# CW308T_STM32F415_Micro.net
KiCad netlist of a schematic drawn in Altium Designer
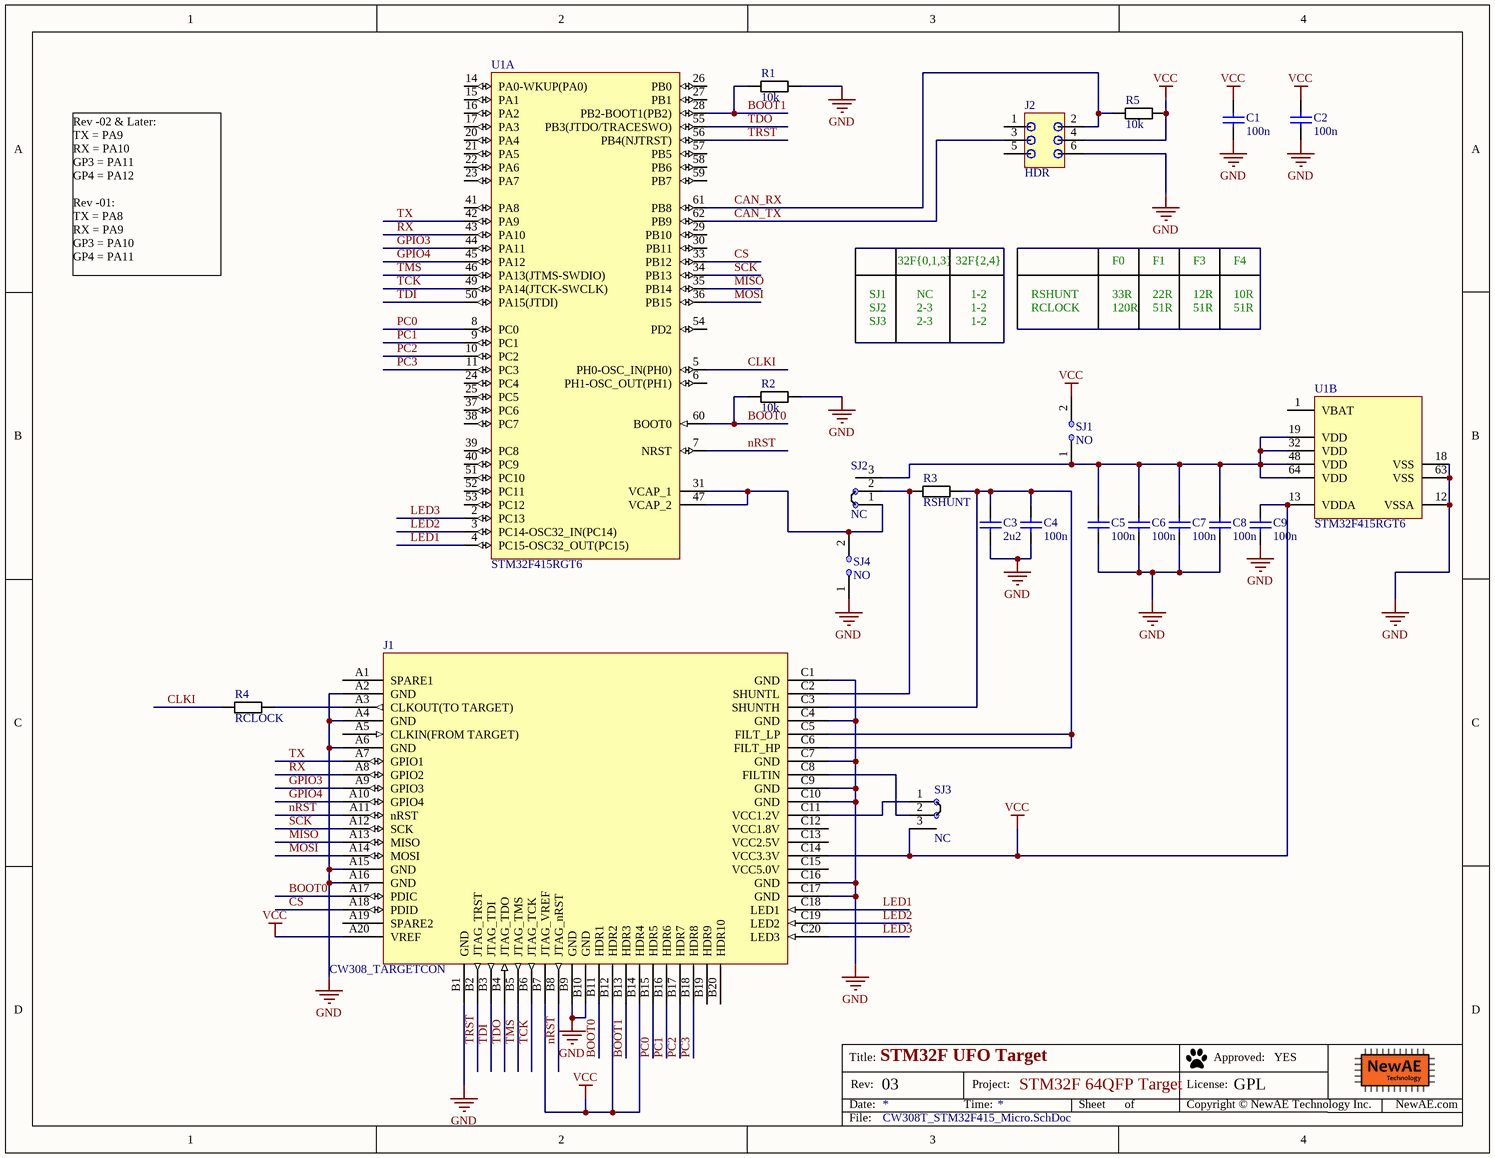
[diagram p0: CW308T_STM32F415_Micro.SchDoc]

(export (version "E")
  (design (tool "Eeschema 10.0.6"))
  (components
    (comp (ref "C1")
      (value "100n")
      (footprint "CAPC0603_M")
      (description "100n, 0603")
      (fields (field (name "PART NUMBER") "CCHIP-100n-0603"))
      (libsource (lib "NewAE_AltiumLib") (part "CAP"))
    )
    (comp (ref "C2")
      (value "100n")
      (footprint "CAPC0603_M")
      (description "100n, 0603")
      (fields (field (name "PART NUMBER") "CCHIP-100n-0603"))
      (libsource (lib "NewAE_AltiumLib") (part "CAP"))
    )
    (comp (ref "C3")
      (value "2u2")
      (footprint "CAPC0603_M")
      (description "2u2, 0603")
      (fields (field (name "PART NUMBER") "CCHIP-2u2-0603"))
      (libsource (lib "NewAE_AltiumLib") (part "CAP"))
    )
    (comp (ref "C4")
      (value "100n")
      (footprint "CAPC0603_M")
      (description "100n, 0603")
      (fields (field (name "PART NUMBER") "CCHIP-100n-0603"))
      (libsource (lib "NewAE_AltiumLib") (part "CAP"))
    )
    (comp (ref "C5")
      (value "100n")
      (footprint "CAPC0603_M")
      (description "100n, 0603")
      (fields (field (name "PART NUMBER") "CCHIP-100n-0603"))
      (libsource (lib "NewAE_AltiumLib") (part "CAP"))
    )
    (comp (ref "C6")
      (value "100n")
      (footprint "CAPC0603_M")
      (description "100n, 0603")
      (fields (field (name "PART NUMBER") "CCHIP-100n-0603"))
      (libsource (lib "NewAE_AltiumLib") (part "CAP"))
    )
    (comp (ref "C7")
      (value "100n")
      (footprint "CAPC0603_M")
      (description "100n, 0603")
      (fields (field (name "PART NUMBER") "CCHIP-100n-0603"))
      (libsource (lib "NewAE_AltiumLib") (part "CAP"))
    )
    (comp (ref "C8")
      (value "100n")
      (footprint "CAPC0603_M")
      (description "100n, 0603")
      (fields (field (name "PART NUMBER") "CCHIP-100n-0603"))
      (libsource (lib "NewAE_AltiumLib") (part "CAP"))
    )
    (comp (ref "C9")
      (value "100n")
      (footprint "CAPC0603_M")
      (description "100n, 0603")
      (fields (field (name "PART NUMBER") "CCHIP-100n-0603"))
      (libsource (lib "NewAE_AltiumLib") (part "CAP"))
    )
    (comp (ref "J1")
      (value "CW308_TARGETCON")
      (footprint "CW308_TBOARD_CONN")
      (description "CW308 \"Standard\" Target Board Connector")
      (fields (field (name "PART NUMBER") "CW308_TBOARD"))
      (libsource (lib "NewAE_AltiumLib") (part "CW308_TBOARD"))
    )
    (comp (ref "J2")
      (value "HDR")
      (footprint "HDR_6PIN_2ROW_SHROUD")
      (description "HDR, Male, 6-Pin, 2 Row, Shrouded")
      (fields (field (name "PART NUMBER") "HDR_6PIN_2ROW_SHROUD"))
      (libsource (lib "NewAE_AltiumLib") (part "CON6_2ROW"))
    )
    (comp (ref "R1")
      (value "10k")
      (footprint "RESC1608X55N")
      (description "10k res, 0603, 1%, 1/10W")
      (fields (field (name "PART NUMBER") "RCHIP-10K-0603") (field (name "TOLERANCE") "1%"))
      (libsource (lib "NewAE_AltiumLib") (part "RES-EU"))
    )
    (comp (ref "R2")
      (value "10k")
      (footprint "RESC1608X55N")
      (description "10k res, 0603, 1%, 1/10W")
      (fields (field (name "PART NUMBER") "RCHIP-10K-0603") (field (name "TOLERANCE") "1%"))
      (libsource (lib "NewAE_AltiumLib") (part "RES-EU"))
    )
    (comp (ref "R3")
      (value "RSHUNT")
      (footprint "RESC1608X55N")
      (description "10R res, 0603, 1%, 1/10W")
      (fields (field (name "PART NUMBER") "RCHIP-10R-0603") (field (name "TOLERANCE") "1%"))
      (libsource (lib "NewAE_AltiumLib") (part "RES-EU"))
    )
    (comp (ref "R4")
      (value "RCLOCK")
      (footprint "RESC1608X55N")
      (description "100R res, 0603, 1%, 1/10W")
      (fields (field (name "PART NUMBER") "RCHIP-100R-0603") (field (name "TOLERANCE") "1%"))
      (libsource (lib "NewAE_AltiumLib") (part "RES-EU"))
    )
    (comp (ref "R5")
      (value "10k")
      (footprint "RESC1608X55N")
      (description "10k res, 0603, 1%, 1/10W")
      (fields (field (name "PART NUMBER") "RCHIP-10K-0603") (field (name "TOLERANCE") "1%"))
      (libsource (lib "NewAE_AltiumLib") (part "RES-EU"))
    )
    (comp (ref "SJ1")
      (value "NO")
      (footprint "SJ_2S_NO")
      (description "Solder Jumper, NO")
      (fields (field (name "PART NUMBER") "SJ_2S_NO"))
      (libsource (lib "NewAE_AltiumLib") (part "SJ_2S_NO"))
    )
    (comp (ref "SJ2")
      (value "NC")
      (footprint "SJ_3S_NC12")
      (description "Solder Jumper, NC")
      (fields (field (name "PART NUMBER") "SJ_3S_12JMP"))
      (libsource (lib "NewAE_AltiumLib") (part "SJ_3S_12JMP"))
    )
    (comp (ref "SJ3")
      (value "NC")
      (footprint "SJ_3S_NC12")
      (description "Solder Jumper, NC")
      (fields (field (name "PART NUMBER") "SJ_3S_12JMP"))
      (libsource (lib "NewAE_AltiumLib") (part "SJ_3S_12JMP"))
    )
    (comp (ref "SJ4")
      (value "NO")
      (footprint "SJ_2S_NO")
      (description "Solder Jumper, NO")
      (fields (field (name "PART NUMBER") "SJ_2S_NO"))
      (libsource (lib "NewAE_AltiumLib") (part "SJ_2S_NO"))
    )
    (comp (ref "U1")
      (value "STM32F415RGT6")
      (footprint "STM-LQFP64_V")
      (fields (field (name "MANUFACTURER") "STMicroelectronics"))
      (libsource (lib "Altium Content Vault") (part "MC-ARM-STM32F4X5-SQ64"))
    )
  )
  (nets
    (net (code "1") (name "/BOOT0") (class "Default")
      (node (ref "J1") (pin "A17") (pinfunction "PDIC_A17") (pintype "bidirectional"))
      (node (ref "J1") (pin "B11") (pinfunction "HDR1_B11") (pintype "passive"))
      (node (ref "R2") (pin "1") (pinfunction "1_1") (pintype "passive"))
      (node (ref "U1") (pin "60") (pinfunction "BOOT0_60") (pintype "input"))
    )
    (net (code "2") (name "/BOOT1") (class "Default")
      (node (ref "J1") (pin "B13") (pinfunction "HDR3_B13") (pintype "passive"))
      (node (ref "R1") (pin "1") (pinfunction "1_1") (pintype "passive"))
      (node (ref "U1") (pin "28") (pinfunction "PB2-BOOT1(PB2)_28") (pintype "bidirectional"))
    )
    (net (code "3") (name "/CAN_RX") (class "Default")
      (node (ref "J2") (pin "2") (pinfunction "2_2") (pintype "passive"))
      (node (ref "R5") (pin "1") (pinfunction "1_1") (pintype "passive"))
      (node (ref "U1") (pin "61") (pinfunction "PB8_61") (pintype "bidirectional"))
    )
    (net (code "4") (name "/CAN_TX") (class "Default")
      (node (ref "J2") (pin "3") (pinfunction "3_3") (pintype "passive"))
      (node (ref "U1") (pin "62") (pinfunction "PB9_62") (pintype "bidirectional"))
    )
    (net (code "5") (name "/CLKI") (class "Default")
      (node (ref "R4") (pin "1") (pinfunction "1_1") (pintype "passive"))
      (node (ref "U1") (pin "5") (pinfunction "PH0-OSC_IN(PH0)_5") (pintype "bidirectional"))
    )
    (net (code "6") (name "/CS") (class "Default")
      (node (ref "J1") (pin "A18") (pinfunction "PDID_A18") (pintype "bidirectional"))
      (node (ref "U1") (pin "33") (pinfunction "PB12_33") (pintype "bidirectional"))
    )
    (net (code "7") (name "/GPIO3") (class "Default")
      (node (ref "J1") (pin "A9") (pinfunction "GPIO3_A9") (pintype "bidirectional"))
      (node (ref "U1") (pin "44") (pinfunction "PA11_44") (pintype "bidirectional"))
    )
    (net (code "8") (name "/GPIO4") (class "Default")
      (node (ref "J1") (pin "A10") (pinfunction "GPIO4_A10") (pintype "bidirectional"))
      (node (ref "U1") (pin "45") (pinfunction "PA12_45") (pintype "bidirectional"))
    )
    (net (code "9") (name "/LED1") (class "Default")
      (node (ref "J1") (pin "C18") (pinfunction "LED1_C18") (pintype "input"))
      (node (ref "U1") (pin "4") (pinfunction "PC15-OSC32_OUT(PC15)_4") (pintype "bidirectional"))
    )
    (net (code "10") (name "/LED2") (class "Default")
      (node (ref "J1") (pin "C19") (pinfunction "LED2_C19") (pintype "input"))
      (node (ref "U1") (pin "3") (pinfunction "PC14-OSC32_IN(PC14)_3") (pintype "bidirectional"))
    )
    (net (code "11") (name "/LED3") (class "Default")
      (node (ref "J1") (pin "C20") (pinfunction "LED3_C20") (pintype "input"))
      (node (ref "U1") (pin "2") (pinfunction "PC13_2") (pintype "bidirectional"))
    )
    (net (code "12") (name "/MISO") (class "Default")
      (node (ref "J1") (pin "A13") (pinfunction "MISO_A13") (pintype "bidirectional"))
      (node (ref "U1") (pin "35") (pinfunction "PB14_35") (pintype "bidirectional"))
    )
    (net (code "13") (name "/MOSI") (class "Default")
      (node (ref "J1") (pin "A14") (pinfunction "MOSI_A14") (pintype "bidirectional"))
      (node (ref "U1") (pin "36") (pinfunction "PB15_36") (pintype "bidirectional"))
    )
    (net (code "14") (name "/PC0") (class "Default")
      (node (ref "J1") (pin "B15") (pinfunction "HDR5_B15") (pintype "passive"))
      (node (ref "U1") (pin "8") (pinfunction "PC0_8") (pintype "bidirectional"))
    )
    (net (code "15") (name "/PC1") (class "Default")
      (node (ref "J1") (pin "B16") (pinfunction "HDR6_B16") (pintype "passive"))
      (node (ref "U1") (pin "9") (pinfunction "PC1_9") (pintype "bidirectional"))
    )
    (net (code "16") (name "/PC2") (class "Default")
      (node (ref "J1") (pin "B17") (pinfunction "HDR7_B17") (pintype "passive"))
      (node (ref "U1") (pin "10") (pinfunction "PC2_10") (pintype "bidirectional"))
    )
    (net (code "17") (name "/PC3") (class "Default")
      (node (ref "J1") (pin "B18") (pinfunction "HDR8_B18") (pintype "passive"))
      (node (ref "U1") (pin "11") (pinfunction "PC3_11") (pintype "bidirectional"))
    )
    (net (code "18") (name "/RX") (class "Default")
      (node (ref "J1") (pin "A8") (pinfunction "GPIO2_A8") (pintype "bidirectional"))
      (node (ref "U1") (pin "43") (pinfunction "PA10_43") (pintype "bidirectional"))
    )
    (net (code "19") (name "/SCK") (class "Default")
      (node (ref "J1") (pin "A12") (pinfunction "SCK_A12") (pintype "bidirectional"))
      (node (ref "U1") (pin "34") (pinfunction "PB13_34") (pintype "bidirectional"))
    )
    (net (code "20") (name "/TCK") (class "Default")
      (node (ref "J1") (pin "B6") (pinfunction "JTAG_TCK_B6") (pintype "output"))
      (node (ref "U1") (pin "49") (pinfunction "PA14(JTCK-SWCLK)_49") (pintype "bidirectional"))
    )
    (net (code "21") (name "/TDI") (class "Default")
      (node (ref "J1") (pin "B3") (pinfunction "JTAG_TDI_B3") (pintype "output"))
      (node (ref "U1") (pin "50") (pinfunction "PA15(JTDI)_50") (pintype "bidirectional"))
    )
    (net (code "22") (name "/TDO") (class "Default")
      (node (ref "J1") (pin "B4") (pinfunction "JTAG_TDO_B4") (pintype "input"))
      (node (ref "U1") (pin "55") (pinfunction "PB3(JTDO/TRACESWO)_55") (pintype "bidirectional"))
    )
    (net (code "23") (name "/TMS") (class "Default")
      (node (ref "J1") (pin "B5") (pinfunction "JTAG_TMS_B5") (pintype "output"))
      (node (ref "U1") (pin "46") (pinfunction "PA13(JTMS-SWDIO)_46") (pintype "bidirectional"))
    )
    (net (code "24") (name "/TRST") (class "Default")
      (node (ref "J1") (pin "B2") (pinfunction "JTAG_TRST_B2") (pintype "output"))
      (node (ref "U1") (pin "56") (pinfunction "PB4(NJTRST)_56") (pintype "bidirectional"))
    )
    (net (code "25") (name "/TX") (class "Default")
      (node (ref "J1") (pin "A7") (pinfunction "GPIO1_A7") (pintype "bidirectional"))
      (node (ref "U1") (pin "42") (pinfunction "PA9_42") (pintype "bidirectional"))
    )
    (net (code "26") (name "/nRST") (class "Default")
      (node (ref "J1") (pin "A11") (pinfunction "nRST_A11") (pintype "bidirectional"))
      (node (ref "J1") (pin "B8") (pinfunction "JTAG_nRST_B8") (pintype "output"))
      (node (ref "U1") (pin "7") (pinfunction "NRST_7") (pintype "bidirectional"))
    )
    (net (code "27") (name "GND") (class "Default")
      (node (ref "C1") (pin "2") (pinfunction "2_2") (pintype "passive"))
      (node (ref "C2") (pin "2") (pinfunction "2_2") (pintype "passive"))
      (node (ref "C3") (pin "2") (pinfunction "2_2") (pintype "passive"))
      (node (ref "C4") (pin "2") (pinfunction "2_2") (pintype "passive"))
      (node (ref "C5") (pin "2") (pinfunction "2_2") (pintype "passive"))
      (node (ref "C6") (pin "2") (pinfunction "2_2") (pintype "passive"))
      (node (ref "C7") (pin "2") (pinfunction "2_2") (pintype "passive"))
      (node (ref "C8") (pin "2") (pinfunction "2_2") (pintype "passive"))
      (node (ref "C9") (pin "2") (pinfunction "2_2") (pintype "passive"))
      (node (ref "J1") (pin "A15") (pinfunction "GND_A15") (pintype "passive"))
      (node (ref "J1") (pin "A16") (pinfunction "GND_A16") (pintype "passive"))
      (node (ref "J1") (pin "A2") (pinfunction "GND_A2") (pintype "passive"))
      (node (ref "J1") (pin "A4") (pinfunction "GND_A4") (pintype "passive"))
      (node (ref "J1") (pin "A6") (pinfunction "GND_A6") (pintype "power_in"))
      (node (ref "J1") (pin "B1") (pinfunction "GND_B1") (pintype "passive"))
      (node (ref "J1") (pin "B10") (pinfunction "GND_B10") (pintype "passive"))
      (node (ref "J1") (pin "B9") (pinfunction "GND_B9") (pintype "passive"))
      (node (ref "J1") (pin "C1") (pinfunction "GND_C1") (pintype "power_in"))
      (node (ref "J1") (pin "C10") (pinfunction "GND_C10") (pintype "power_in"))
      (node (ref "J1") (pin "C16") (pinfunction "GND_C16") (pintype "power_in"))
      (node (ref "J1") (pin "C17") (pinfunction "GND_C17") (pintype "power_in"))
      (node (ref "J1") (pin "C4") (pinfunction "GND_C4") (pintype "power_in"))
      (node (ref "J1") (pin "C7") (pinfunction "GND_C7") (pintype "power_in"))
      (node (ref "J1") (pin "C9") (pinfunction "GND_C9") (pintype "power_in"))
      (node (ref "J2") (pin "6") (pinfunction "6_6") (pintype "passive"))
      (node (ref "R1") (pin "2") (pinfunction "2_2") (pintype "passive"))
      (node (ref "R2") (pin "2") (pinfunction "2_2") (pintype "passive"))
      (node (ref "SJ4") (pin "1") (pinfunction "1_1") (pintype "passive"))
      (node (ref "U1") (pin "12") (pinfunction "VSSA_12") (pintype "power_in"))
      (node (ref "U1") (pin "18") (pinfunction "VSS_18") (pintype "power_in"))
      (node (ref "U1") (pin "63") (pinfunction "VSS_63") (pintype "power_in"))
    )
    (net (code "28") (name "Net-(C5-Pad1)") (class "Default")
      (node (ref "C5") (pin "1") (pinfunction "1_1") (pintype "passive"))
      (node (ref "C6") (pin "1") (pinfunction "1_1") (pintype "passive"))
      (node (ref "C7") (pin "1") (pinfunction "1_1") (pintype "passive"))
      (node (ref "C8") (pin "1") (pinfunction "1_1") (pintype "passive"))
      (node (ref "SJ1") (pin "1") (pinfunction "1_1") (pintype "passive"))
      (node (ref "SJ2") (pin "3") (pinfunction "3_3") (pintype "passive"))
      (node (ref "U1") (pin "19") (pinfunction "VDD_19") (pintype "power_in"))
      (node (ref "U1") (pin "32") (pinfunction "VDD_32") (pintype "power_in"))
      (node (ref "U1") (pin "48") (pinfunction "VDD_48") (pintype "power_in"))
      (node (ref "U1") (pin "64") (pinfunction "VDD_64") (pintype "power_in"))
    )
    (net (code "29") (name "Net-(J1-CLKOUT(TO_TARGET))") (class "Default")
      (node (ref "J1") (pin "A3") (pinfunction "CLKOUT(TO_TARGET)_A3") (pintype "output"))
      (node (ref "R4") (pin "2") (pinfunction "2_2") (pintype "passive"))
    )
    (net (code "30") (name "Net-(J1-FILTIN)") (class "Default")
      (node (ref "J1") (pin "C8") (pinfunction "FILTIN_C8") (pintype "passive"))
      (node (ref "SJ3") (pin "2") (pinfunction "2_2") (pintype "passive"))
    )
    (net (code "31") (name "Net-(J1-FILT_HP)") (class "Default")
      (node (ref "C3") (pin "1") (pinfunction "1_1") (pintype "passive"))
      (node (ref "C4") (pin "1") (pinfunction "1_1") (pintype "passive"))
      (node (ref "J1") (pin "C3") (pinfunction "SHUNTH_C3") (pintype "passive"))
      (node (ref "J1") (pin "C5") (pinfunction "FILT_LP_C5") (pintype "passive"))
      (node (ref "J1") (pin "C6") (pinfunction "FILT_HP_C6") (pintype "passive"))
      (node (ref "R3") (pin "2") (pinfunction "2_2") (pintype "passive"))
    )
    (net (code "32") (name "Net-(J1-SHUNTL)") (class "Default")
      (node (ref "J1") (pin "C2") (pinfunction "SHUNTL_C2") (pintype "passive"))
      (node (ref "R3") (pin "1") (pinfunction "1_1") (pintype "passive"))
      (node (ref "SJ2") (pin "2") (pinfunction "2_2") (pintype "passive"))
    )
    (net (code "33") (name "Net-(J1-VCC1.2V)") (class "Default")
      (node (ref "J1") (pin "C11") (pinfunction "VCC1.2V_C11") (pintype "power_in"))
      (node (ref "SJ3") (pin "1") (pinfunction "1_1") (pintype "passive"))
    )
    (net (code "34") (name "Net-(U1A-VCAP_1)") (class "Default")
      (node (ref "SJ2") (pin "1") (pinfunction "1_1") (pintype "passive"))
      (node (ref "SJ4") (pin "2") (pinfunction "2_2") (pintype "passive"))
      (node (ref "U1") (pin "31") (pinfunction "VCAP_1_31") (pintype "power_in"))
      (node (ref "U1") (pin "47") (pinfunction "VCAP_2_47") (pintype "power_in"))
    )
    (net (code "35") (name "VCC") (class "Default")
      (node (ref "C1") (pin "1") (pinfunction "1_1") (pintype "passive"))
      (node (ref "C2") (pin "1") (pinfunction "1_1") (pintype "passive"))
      (node (ref "C9") (pin "1") (pinfunction "1_1") (pintype "passive"))
      (node (ref "J1") (pin "A20") (pinfunction "VREF_A20") (pintype "tri_state"))
      (node (ref "J1") (pin "B12") (pinfunction "HDR2_B12") (pintype "passive"))
      (node (ref "J1") (pin "B14") (pinfunction "HDR4_B14") (pintype "passive"))
      (node (ref "J1") (pin "B7") (pinfunction "JTAG_VREF_B7") (pintype "tri_state"))
      (node (ref "J1") (pin "C14") (pinfunction "VCC3.3V_C14") (pintype "power_in"))
      (node (ref "J2") (pin "4") (pinfunction "4_4") (pintype "passive"))
      (node (ref "R5") (pin "2") (pinfunction "2_2") (pintype "passive"))
      (node (ref "SJ1") (pin "2") (pinfunction "2_2") (pintype "passive"))
      (node (ref "SJ3") (pin "3") (pinfunction "3_3") (pintype "passive"))
      (node (ref "U1") (pin "13") (pinfunction "VDDA_13") (pintype "power_in"))
    )
    (net (code "36") (name "unconnected-(J1-CLKIN(FROM_TARGET)-PadA5)") (class "Default")
      (node (ref "J1") (pin "A5") (pinfunction "CLKIN(FROM_TARGET)_A5") (pintype "input"))
    )
    (net (code "37") (name "unconnected-(J1-HDR9-PadB19)") (class "Default")
      (node (ref "J1") (pin "B19") (pinfunction "HDR9_B19") (pintype "passive"))
    )
    (net (code "38") (name "unconnected-(J1-HDR10-PadB20)") (class "Default")
      (node (ref "J1") (pin "B20") (pinfunction "HDR10_B20") (pintype "passive"))
    )
    (net (code "39") (name "unconnected-(J1-SPARE1-PadA1)") (class "Default")
      (node (ref "J1") (pin "A1") (pinfunction "SPARE1_A1") (pintype "passive"))
    )
    (net (code "40") (name "unconnected-(J1-SPARE2-PadA19)") (class "Default")
      (node (ref "J1") (pin "A19") (pinfunction "SPARE2_A19") (pintype "passive"))
    )
    (net (code "41") (name "unconnected-(J1-VCC1.8V-PadC12)") (class "Default")
      (node (ref "J1") (pin "C12") (pinfunction "VCC1.8V_C12") (pintype "power_in"))
    )
    (net (code "42") (name "unconnected-(J1-VCC2.5V-PadC13)") (class "Default")
      (node (ref "J1") (pin "C13") (pinfunction "VCC2.5V_C13") (pintype "power_in"))
    )
    (net (code "43") (name "unconnected-(J1-VCC5.0V-PadC15)") (class "Default")
      (node (ref "J1") (pin "C15") (pinfunction "VCC5.0V_C15") (pintype "power_in"))
    )
    (net (code "44") (name "unconnected-(J2-Pad1)") (class "Default")
      (node (ref "J2") (pin "1") (pinfunction "1_1") (pintype "passive"))
    )
    (net (code "45") (name "unconnected-(J2-Pad5)") (class "Default")
      (node (ref "J2") (pin "5") (pinfunction "5_5") (pintype "passive"))
    )
    (net (code "46") (name "unconnected-(U1A-PA0-WKUP(PA0)-Pad14)") (class "Default")
      (node (ref "U1") (pin "14") (pinfunction "PA0-WKUP(PA0)_14") (pintype "bidirectional"))
    )
    (net (code "47") (name "unconnected-(U1A-PA1-Pad15)") (class "Default")
      (node (ref "U1") (pin "15") (pinfunction "PA1_15") (pintype "bidirectional"))
    )
    (net (code "48") (name "unconnected-(U1A-PA2-Pad16)") (class "Default")
      (node (ref "U1") (pin "16") (pinfunction "PA2_16") (pintype "bidirectional"))
    )
    (net (code "49") (name "unconnected-(U1A-PA3-Pad17)") (class "Default")
      (node (ref "U1") (pin "17") (pinfunction "PA3_17") (pintype "bidirectional"))
    )
    (net (code "50") (name "unconnected-(U1A-PA4-Pad20)") (class "Default")
      (node (ref "U1") (pin "20") (pinfunction "PA4_20") (pintype "bidirectional"))
    )
    (net (code "51") (name "unconnected-(U1A-PA5-Pad21)") (class "Default")
      (node (ref "U1") (pin "21") (pinfunction "PA5_21") (pintype "bidirectional"))
    )
    (net (code "52") (name "unconnected-(U1A-PA6-Pad22)") (class "Default")
      (node (ref "U1") (pin "22") (pinfunction "PA6_22") (pintype "bidirectional"))
    )
    (net (code "53") (name "unconnected-(U1A-PA7-Pad23)") (class "Default")
      (node (ref "U1") (pin "23") (pinfunction "PA7_23") (pintype "bidirectional"))
    )
    (net (code "54") (name "unconnected-(U1A-PA8-Pad41)") (class "Default")
      (node (ref "U1") (pin "41") (pinfunction "PA8_41") (pintype "bidirectional"))
    )
    (net (code "55") (name "unconnected-(U1A-PB0-Pad26)") (class "Default")
      (node (ref "U1") (pin "26") (pinfunction "PB0_26") (pintype "bidirectional"))
    )
    (net (code "56") (name "unconnected-(U1A-PB1-Pad27)") (class "Default")
      (node (ref "U1") (pin "27") (pinfunction "PB1_27") (pintype "bidirectional"))
    )
    (net (code "57") (name "unconnected-(U1A-PB5-Pad57)") (class "Default")
      (node (ref "U1") (pin "57") (pinfunction "PB5_57") (pintype "bidirectional"))
    )
    (net (code "58") (name "unconnected-(U1A-PB6-Pad58)") (class "Default")
      (node (ref "U1") (pin "58") (pinfunction "PB6_58") (pintype "bidirectional"))
    )
    (net (code "59") (name "unconnected-(U1A-PB7-Pad59)") (class "Default")
      (node (ref "U1") (pin "59") (pinfunction "PB7_59") (pintype "bidirectional"))
    )
    (net (code "60") (name "unconnected-(U1A-PB10-Pad29)") (class "Default")
      (node (ref "U1") (pin "29") (pinfunction "PB10_29") (pintype "bidirectional"))
    )
    (net (code "61") (name "unconnected-(U1A-PB11-Pad30)") (class "Default")
      (node (ref "U1") (pin "30") (pinfunction "PB11_30") (pintype "bidirectional"))
    )
    (net (code "62") (name "unconnected-(U1A-PC4-Pad24)") (class "Default")
      (node (ref "U1") (pin "24") (pinfunction "PC4_24") (pintype "bidirectional"))
    )
    (net (code "63") (name "unconnected-(U1A-PC5-Pad25)") (class "Default")
      (node (ref "U1") (pin "25") (pinfunction "PC5_25") (pintype "bidirectional"))
    )
    (net (code "64") (name "unconnected-(U1A-PC6-Pad37)") (class "Default")
      (node (ref "U1") (pin "37") (pinfunction "PC6_37") (pintype "bidirectional"))
    )
    (net (code "65") (name "unconnected-(U1A-PC7-Pad38)") (class "Default")
      (node (ref "U1") (pin "38") (pinfunction "PC7_38") (pintype "bidirectional"))
    )
    (net (code "66") (name "unconnected-(U1A-PC8-Pad39)") (class "Default")
      (node (ref "U1") (pin "39") (pinfunction "PC8_39") (pintype "bidirectional"))
    )
    (net (code "67") (name "unconnected-(U1A-PC9-Pad40)") (class "Default")
      (node (ref "U1") (pin "40") (pinfunction "PC9_40") (pintype "bidirectional"))
    )
    (net (code "68") (name "unconnected-(U1A-PC10-Pad51)") (class "Default")
      (node (ref "U1") (pin "51") (pinfunction "PC10_51") (pintype "bidirectional"))
    )
    (net (code "69") (name "unconnected-(U1A-PC11-Pad52)") (class "Default")
      (node (ref "U1") (pin "52") (pinfunction "PC11_52") (pintype "bidirectional"))
    )
    (net (code "70") (name "unconnected-(U1A-PC12-Pad53)") (class "Default")
      (node (ref "U1") (pin "53") (pinfunction "PC12_53") (pintype "bidirectional"))
    )
    (net (code "71") (name "unconnected-(U1A-PD2-Pad54)") (class "Default")
      (node (ref "U1") (pin "54") (pinfunction "PD2_54") (pintype "bidirectional"))
    )
    (net (code "72") (name "unconnected-(U1A-PH1-OSC_OUT(PH1)-Pad6)") (class "Default")
      (node (ref "U1") (pin "6") (pinfunction "PH1-OSC_OUT(PH1)_6") (pintype "bidirectional"))
    )
    (net (code "73") (name "unconnected-(U1B-VBAT-Pad1)") (class "Default")
      (node (ref "U1") (pin "1") (pinfunction "VBAT_1") (pintype "power_in"))
    )
  )
)
